# DigitalClock.net
KiCad netlist of a schematic drawn in Altium Designer
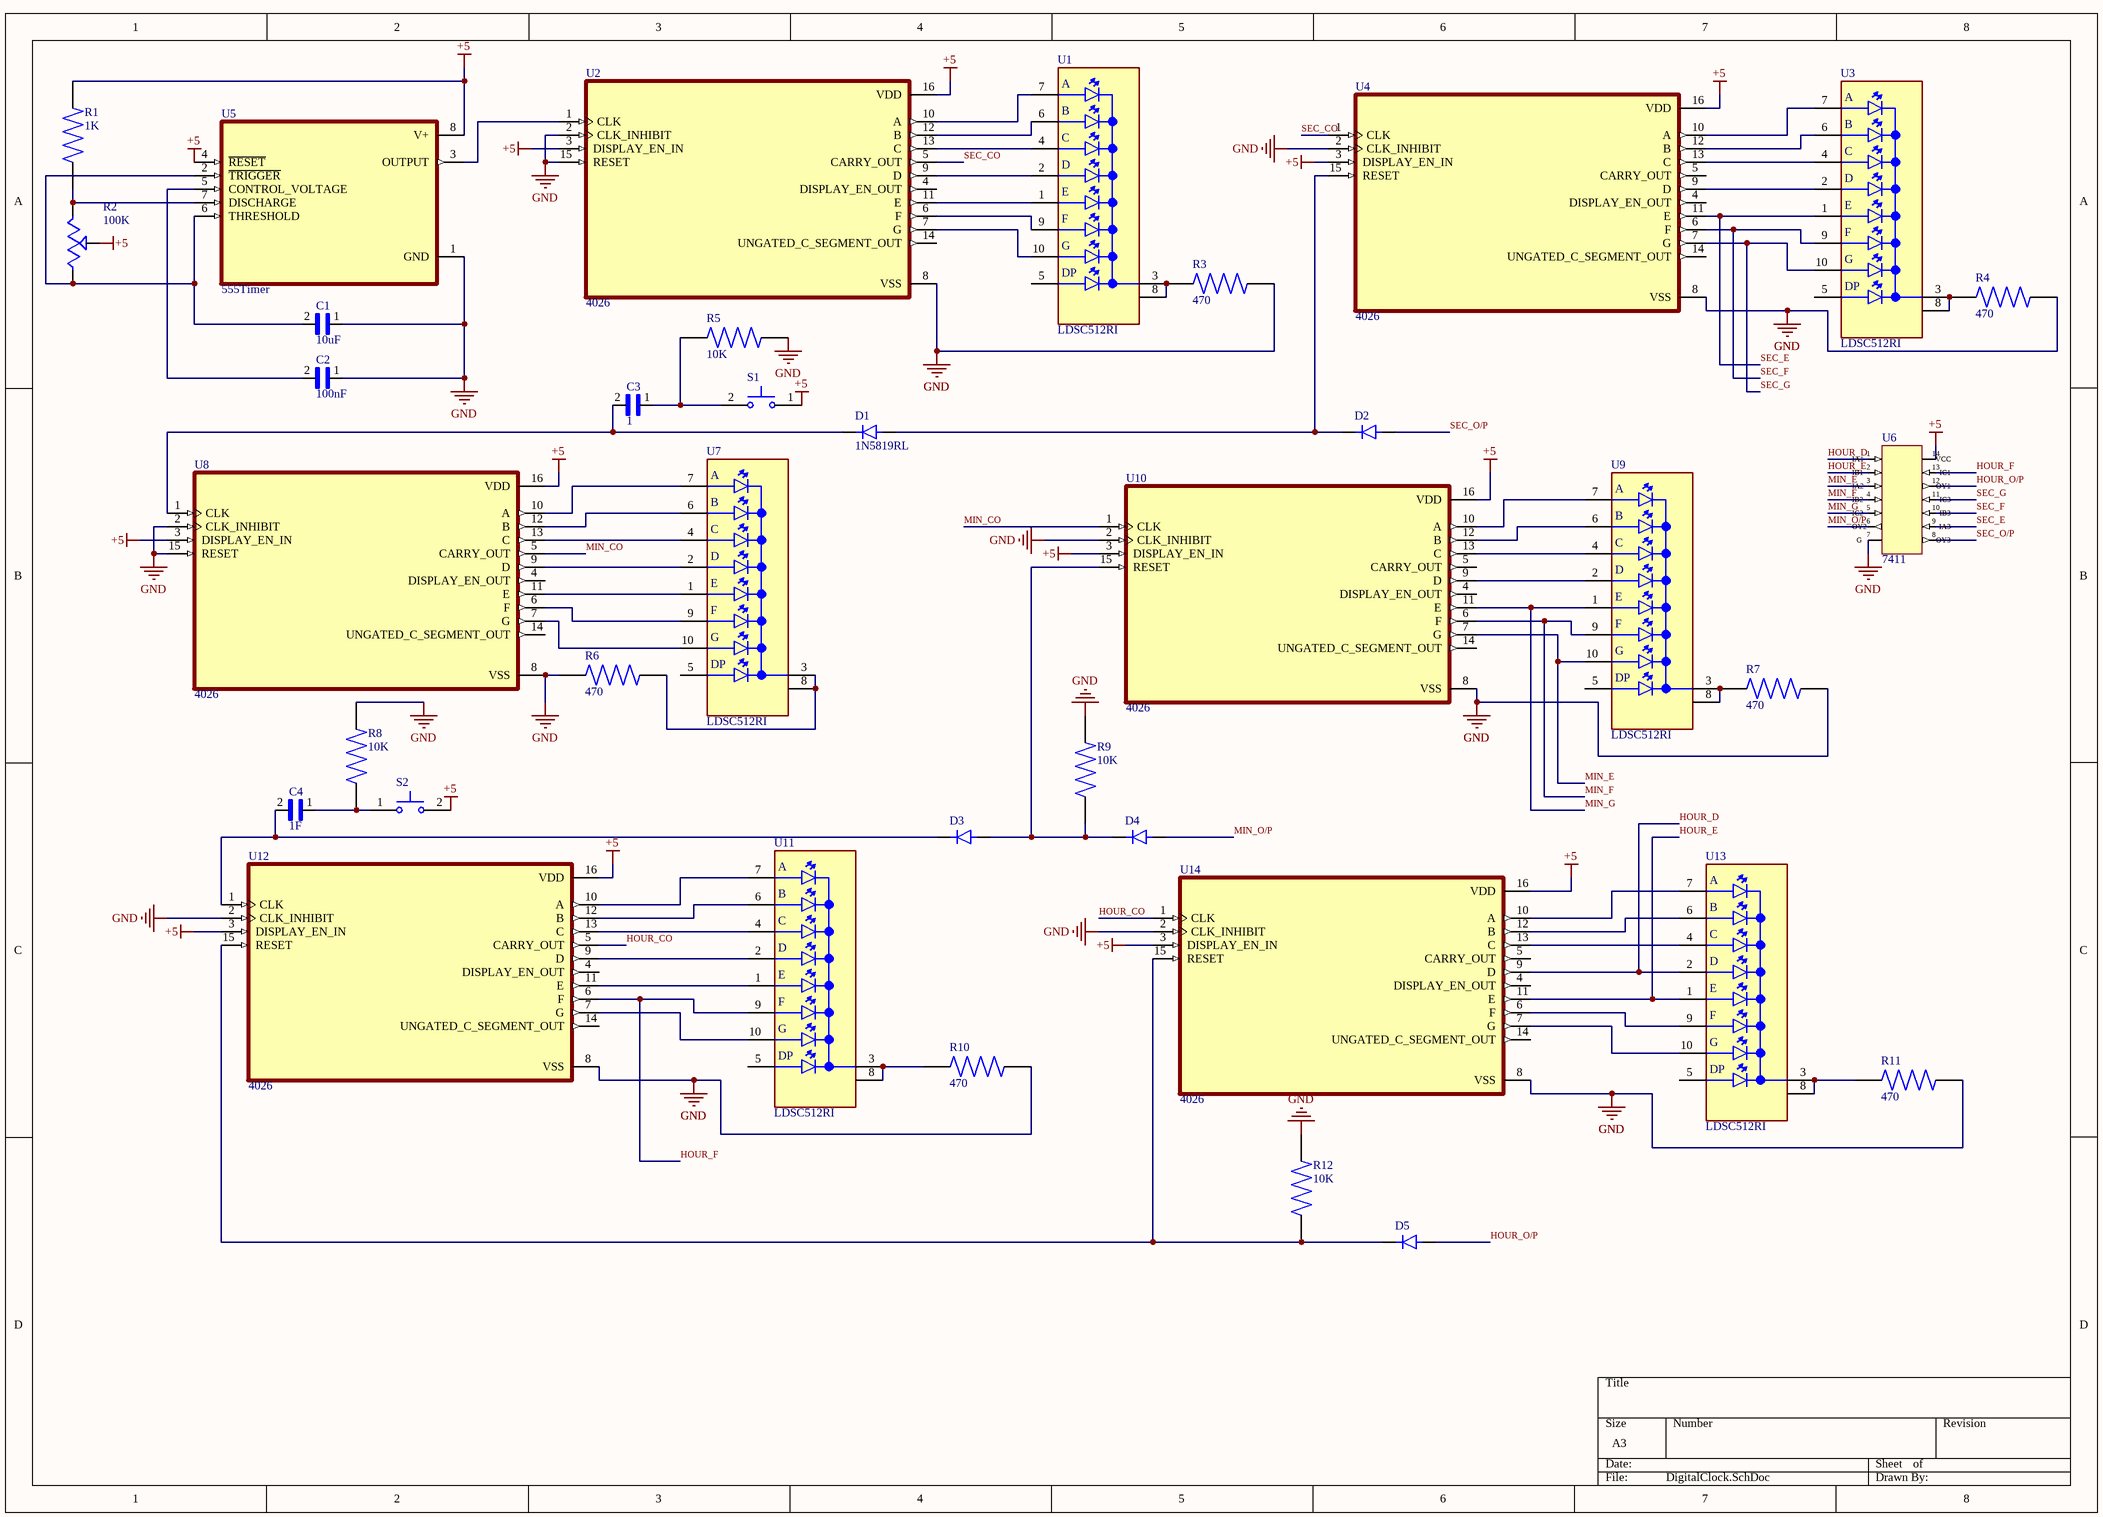
[diagram p0: DigitalClock.SchDoc]

(export (version "E")
  (design (tool "Eeschema 10.0.6"))
  (components
    (comp (ref "C1")
      (value "10uF")
      (footprint "CAPC1005X55N")
      (fields (field (name "MP") "C0402H102J5GACTU"))
      (libsource (lib "Capacitor") (part "C0402H102J5GACTU"))
    )
    (comp (ref "C2")
      (value "100nF")
      (footprint "CAPC1005X55N")
      (fields (field (name "MP") "C0402H102J5GACTU"))
      (libsource (lib "Capacitor") (part "C0402H102J5GACTU"))
    )
    (comp (ref "C3")
      (value "1")
      (footprint "CAPC1005X55N")
      (fields (field (name "MP") "C0402H102J5GACTU"))
      (libsource (lib "Capacitor") (part "C0402H102J5GACTU"))
    )
    (comp (ref "C4")
      (value "1F")
      (footprint "CAPC1005X55N")
      (fields (field (name "MP") "C0402H102J5GACTU"))
      (libsource (lib "Capacitor") (part "C0402H102J5GACTU"))
    )
    (comp (ref "D1")
      (value "1N5819RL")
      (footprint "DIOAD1036W78L470D235")
      (description "Diode Schottky 40 V 1A Through Hole Axial")
      (fields (field (name "MF") "ON Semiconductor"))
      (libsource (lib "Diode_Rectifier_Schottky") (part "1N5819RL"))
    )
    (comp (ref "D2")
      (value "1N5819RL")
      (footprint "DIOAD1036W78L470D235")
      (description "Diode Schottky 40 V 1A Through Hole Axial")
      (fields (field (name "MF") "ON Semiconductor"))
      (libsource (lib "Diode_Rectifier_Schottky") (part "1N5819RL"))
    )
    (comp (ref "D3")
      (value "1N5819RL")
      (footprint "DIOAD1036W78L470D235")
      (description "Diode Schottky 40 V 1A Through Hole Axial")
      (fields (field (name "MF") "ON Semiconductor"))
      (libsource (lib "Diode_Rectifier_Schottky") (part "1N5819RL"))
    )
    (comp (ref "D4")
      (value "1N5819RL")
      (footprint "DIOAD1036W78L470D235")
      (description "Diode Schottky 40 V 1A Through Hole Axial")
      (fields (field (name "MF") "ON Semiconductor"))
      (libsource (lib "Diode_Rectifier_Schottky") (part "1N5819RL"))
    )
    (comp (ref "D5")
      (value "1N5819RL")
      (footprint "DIOAD1036W78L470D235")
      (description "Diode Schottky 40 V 1A Through Hole Axial")
      (fields (field (name "MF") "ON Semiconductor"))
      (libsource (lib "Diode_Rectifier_Schottky") (part "1N5819RL"))
    )
    (comp (ref "R1")
      (value "1K")
      (footprint "RESAD1100W55L680D260")
      (fields (field (name "MP") "ERJU01J683C"))
      (libsource (lib "Resistance") (part "ERJU01J683C"))
    )
    (comp (ref "R2")
      (value "100K")
      (footprint "POT_RD901F-40-15R1-B100K-00DL1")
      (description "Potentiometers 9mm Linear 100K Round Shaft")
      (fields (field (name "MF") "Alpha (Taiwan)") (field (name "MP") "RD901F-40-15R1-B100K-00DL1"))
      (libsource (lib "Potentiometer_02") (part "RD901F-40-15R1-B100K-00DL1"))
    )
    (comp (ref "R3")
      (value "470")
      (footprint "TO508P1060X500X1900-2")
      (fields (field (name "MP") "ERJU01J683C"))
      (libsource (lib "Resistance") (part "ERJU01J683C"))
    )
    (comp (ref "R4")
      (value "470")
      (footprint "RES_ERJU01J683C")
      (fields (field (name "MP") "ERJU01J683C"))
      (libsource (lib "Resistance") (part "ERJU01J683C"))
    )
    (comp (ref "R5")
      (value "10K")
      (footprint "RES_ERJU01J683C")
      (fields (field (name "MP") "ERJU01J683C"))
      (libsource (lib "Resistance") (part "ERJU01J683C"))
    )
    (comp (ref "R6")
      (value "470")
      (footprint "RES_ERJU01J683C")
      (fields (field (name "MP") "ERJU01J683C"))
      (libsource (lib "Resistance") (part "ERJU01J683C"))
    )
    (comp (ref "R7")
      (value "470")
      (footprint "RES_ERJU01J683C")
      (fields (field (name "MP") "ERJU01J683C"))
      (libsource (lib "Resistance") (part "ERJU01J683C"))
    )
    (comp (ref "R8")
      (value "10K")
      (footprint "RES_ERJU01J683C")
      (fields (field (name "MP") "ERJU01J683C"))
      (libsource (lib "Resistance") (part "ERJU01J683C"))
    )
    (comp (ref "R9")
      (value "10K")
      (footprint "RES_ERJU01J683C")
      (fields (field (name "MP") "ERJU01J683C"))
      (libsource (lib "Resistance") (part "ERJU01J683C"))
    )
    (comp (ref "R10")
      (value "470")
      (footprint "RES_ERJU01J683C")
      (fields (field (name "MP") "ERJU01J683C"))
      (libsource (lib "Resistance") (part "ERJU01J683C"))
    )
    (comp (ref "R11")
      (value "470")
      (footprint "RES_ERJU01J683C")
      (fields (field (name "MP") "ERJU01J683C"))
      (libsource (lib "Resistance") (part "ERJU01J683C"))
    )
    (comp (ref "R12")
      (value "10K")
      (footprint "RES_ERJU01J683C")
      (fields (field (name "MP") "ERJU01J683C"))
      (libsource (lib "Resistance") (part "ERJU01J683C"))
    )
    (comp (ref "S1")
      (value "BUTT-2")
      (footprint "SW_BUTT-2")
      (description "Tactile Switches MINI PUSH BUTTON SWITCH 2-PIN QTY. 4")
      (fields (field (name "MF") "Gravitech"))
      (libsource (lib "PushButton02") (part "BUTT-2"))
    )
    (comp (ref "S2")
      (value "BUTT-2")
      (footprint "SW_BUTT-2")
      (description "Tactile Switches MINI PUSH BUTTON SWITCH 2-PIN QTY. 4")
      (fields (field (name "MF") "Gravitech"))
      (libsource (lib "PushButton02") (part "BUTT-2"))
    )
    (comp (ref "U1")
      (value "LDSC512RI")
      (footprint "LED_LDSC512RI")
      (fields (field (name "MF") "Lumex Optoelectronics"))
      (libsource (lib "LDSC512RI") (part "LDSC512RI"))
    )
    (comp (ref "U2")
      (value "4026")
      (footprint "DIP794W45P254L1969H508Q16")
      (fields (field (name "MF") "Texas Instruments") (field (name "MP") "CD4026BE"))
      (libsource (lib "DecadeCounter_CD4026") (part "CD4026BE"))
    )
    (comp (ref "U3")
      (value "LDSC512RI")
      (footprint "LED_LDSC512RI")
      (fields (field (name "MF") "Lumex Optoelectronics"))
      (libsource (lib "LDSC512RI") (part "LDSC512RI"))
    )
    (comp (ref "U4")
      (value "4026")
      (footprint "DIP794W45P254L1969H508Q16")
      (fields (field (name "MF") "Texas Instruments") (field (name "MP") "CD4026BE"))
      (libsource (lib "DecadeCounter_CD4026") (part "CD4026BE"))
    )
    (comp (ref "U5")
      (value "555Timer")
      (footprint "SOIC127P599X175-8N")
      (description "Worlds smallest 555 timer with low power, high accuracy and a Fmax of 3MHz 8-SOIC -40 to 85")
      (fields (field (name "MP") "LMC555CM/NOPB") (field (name "MF") "Texas Instruments"))
      (libsource (lib "555Timer") (part "LMC555CM/NOPB"))
    )
    (comp (ref "U6")
      (value "7411")
      (footprint "IC 7411")
      (description "Three Input AND Gate")
      (libsource (lib "IC7411") (part "7411"))
    )
    (comp (ref "U7")
      (value "LDSC512RI")
      (footprint "LED_LDSC512RI")
      (fields (field (name "MF") "Lumex Optoelectronics"))
      (libsource (lib "LDSC512RI") (part "LDSC512RI"))
    )
    (comp (ref "U8")
      (value "4026")
      (footprint "DIP794W45P254L1969H508Q16")
      (fields (field (name "MF") "Texas Instruments") (field (name "MP") "CD4026BE"))
      (libsource (lib "DecadeCounter_CD4026") (part "CD4026BE"))
    )
    (comp (ref "U9")
      (value "LDSC512RI")
      (footprint "LED_LDSC512RI")
      (fields (field (name "MF") "Lumex Optoelectronics"))
      (libsource (lib "LDSC512RI") (part "LDSC512RI"))
    )
    (comp (ref "U10")
      (value "4026")
      (footprint "DIP794W45P254L1969H508Q16")
      (fields (field (name "MF") "Texas Instruments") (field (name "MP") "CD4026BE"))
      (libsource (lib "DecadeCounter_CD4026") (part "CD4026BE"))
    )
    (comp (ref "U11")
      (value "LDSC512RI")
      (footprint "LED_LDSC512RI")
      (fields (field (name "MF") "Lumex Optoelectronics"))
      (libsource (lib "LDSC512RI") (part "LDSC512RI"))
    )
    (comp (ref "U12")
      (value "4026")
      (footprint "DIP794W45P254L1969H508Q16")
      (fields (field (name "MF") "Texas Instruments") (field (name "MP") "CD4026BE"))
      (libsource (lib "DecadeCounter_CD4026") (part "CD4026BE"))
    )
    (comp (ref "U13")
      (value "LDSC512RI")
      (footprint "LED_LDSC512RI")
      (fields (field (name "MF") "Lumex Optoelectronics"))
      (libsource (lib "LDSC512RI") (part "LDSC512RI"))
    )
    (comp (ref "U14")
      (value "4026")
      (footprint "DIP794W45P254L1969H508Q16")
      (fields (field (name "MF") "Texas Instruments") (field (name "MP") "CD4026BE"))
      (libsource (lib "DecadeCounter_CD4026") (part "CD4026BE"))
    )
  )
  (nets
    (net (code "1") (name "+5") (class "Default")
      (node (ref "R1") (pin "2") (pinfunction "2_2") (pintype "passive"))
      (node (ref "R2") (pin "2") (pinfunction "2_2") (pintype "passive"))
      (node (ref "S1") (pin "1") (pinfunction "1_1") (pintype "passive"))
      (node (ref "S2") (pin "2") (pinfunction "2_2") (pintype "passive"))
      (node (ref "U10") (pin "16") (pinfunction "VDD_16") (pintype "power_in"))
      (node (ref "U10") (pin "3") (pinfunction "DISPLAY_EN_IN_3") (pintype "input"))
      (node (ref "U12") (pin "16") (pinfunction "VDD_16") (pintype "power_in"))
      (node (ref "U12") (pin "3") (pinfunction "DISPLAY_EN_IN_3") (pintype "input"))
      (node (ref "U14") (pin "16") (pinfunction "VDD_16") (pintype "power_in"))
      (node (ref "U14") (pin "3") (pinfunction "DISPLAY_EN_IN_3") (pintype "input"))
      (node (ref "U2") (pin "16") (pinfunction "VDD_16") (pintype "power_in"))
      (node (ref "U2") (pin "3") (pinfunction "DISPLAY_EN_IN_3") (pintype "input"))
      (node (ref "U4") (pin "16") (pinfunction "VDD_16") (pintype "power_in"))
      (node (ref "U4") (pin "3") (pinfunction "DISPLAY_EN_IN_3") (pintype "input"))
      (node (ref "U5") (pin "4") (pinfunction "~{RESET}_4") (pintype "input"))
      (node (ref "U5") (pin "8") (pinfunction "V+_8") (pintype "power_in"))
      (node (ref "U6") (pin "14") (pinfunction "VCC_14") (pintype "power_in"))
      (node (ref "U8") (pin "16") (pinfunction "VDD_16") (pintype "power_in"))
      (node (ref "U8") (pin "3") (pinfunction "DISPLAY_EN_IN_3") (pintype "input"))
    )
    (net (code "2") (name "/HOUR_CO") (class "Default")
      (node (ref "U12") (pin "5") (pinfunction "CARRY_OUT_5") (pintype "output"))
      (node (ref "U14") (pin "1") (pinfunction "CLK_1") (pintype "input"))
    )
    (net (code "3") (name "/HOUR_D") (class "Default")
      (node (ref "U13") (pin "2") (pinfunction "D_2") (pintype "passive"))
      (node (ref "U14") (pin "9") (pinfunction "D_9") (pintype "output"))
      (node (ref "U6") (pin "1") (pinfunction "IA1_1") (pintype "input"))
    )
    (net (code "4") (name "/HOUR_E") (class "Default")
      (node (ref "U13") (pin "1") (pinfunction "E_1") (pintype "passive"))
      (node (ref "U14") (pin "11") (pinfunction "E_11") (pintype "output"))
      (node (ref "U6") (pin "2") (pinfunction "IB1_2") (pintype "input"))
    )
    (net (code "5") (name "/HOUR_F") (class "Default")
      (node (ref "U11") (pin "9") (pinfunction "F_9") (pintype "passive"))
      (node (ref "U12") (pin "6") (pinfunction "F_6") (pintype "output"))
      (node (ref "U6") (pin "13") (pinfunction "IC1_13") (pintype "input"))
    )
    (net (code "6") (name "/HOUR_O{slash}P") (class "Default")
      (node (ref "D5") (pin "A") (pinfunction "A_A") (pintype "passive"))
      (node (ref "U6") (pin "12") (pinfunction "OY1_12") (pintype "output"))
    )
    (net (code "7") (name "/MIN_CO") (class "Default")
      (node (ref "U10") (pin "1") (pinfunction "CLK_1") (pintype "input"))
      (node (ref "U8") (pin "5") (pinfunction "CARRY_OUT_5") (pintype "output"))
    )
    (net (code "8") (name "/MIN_E") (class "Default")
      (node (ref "U10") (pin "7") (pinfunction "G_7") (pintype "output"))
      (node (ref "U6") (pin "3") (pinfunction "IA2_3") (pintype "input"))
      (node (ref "U9") (pin "10") (pinfunction "G_10") (pintype "passive"))
    )
    (net (code "9") (name "/MIN_F") (class "Default")
      (node (ref "U10") (pin "6") (pinfunction "F_6") (pintype "output"))
      (node (ref "U6") (pin "4") (pinfunction "IB2_4") (pintype "input"))
      (node (ref "U9") (pin "9") (pinfunction "F_9") (pintype "passive"))
    )
    (net (code "10") (name "/MIN_G") (class "Default")
      (node (ref "U10") (pin "11") (pinfunction "E_11") (pintype "output"))
      (node (ref "U6") (pin "5") (pinfunction "IC2_5") (pintype "input"))
      (node (ref "U9") (pin "1") (pinfunction "E_1") (pintype "passive"))
    )
    (net (code "11") (name "/MIN_O{slash}P") (class "Default")
      (node (ref "D4") (pin "A") (pinfunction "A_A") (pintype "passive"))
      (node (ref "U6") (pin "6") (pinfunction "OY2_6") (pintype "output"))
    )
    (net (code "12") (name "/SEC_CO") (class "Default")
      (node (ref "U2") (pin "5") (pinfunction "CARRY_OUT_5") (pintype "output"))
      (node (ref "U4") (pin "1") (pinfunction "CLK_1") (pintype "input"))
    )
    (net (code "13") (name "/SEC_E") (class "Default")
      (node (ref "U3") (pin "1") (pinfunction "E_1") (pintype "passive"))
      (node (ref "U4") (pin "11") (pinfunction "E_11") (pintype "output"))
      (node (ref "U6") (pin "9") (pinfunction "IA3_9") (pintype "input"))
    )
    (net (code "14") (name "/SEC_F") (class "Default")
      (node (ref "U3") (pin "9") (pinfunction "F_9") (pintype "passive"))
      (node (ref "U4") (pin "6") (pinfunction "F_6") (pintype "output"))
      (node (ref "U6") (pin "10") (pinfunction "IB3_10") (pintype "input"))
    )
    (net (code "15") (name "/SEC_G") (class "Default")
      (node (ref "U3") (pin "10") (pinfunction "G_10") (pintype "passive"))
      (node (ref "U4") (pin "7") (pinfunction "G_7") (pintype "output"))
      (node (ref "U6") (pin "11") (pinfunction "IC3_11") (pintype "input"))
    )
    (net (code "16") (name "/SEC_O{slash}P") (class "Default")
      (node (ref "D2") (pin "A") (pinfunction "A_A") (pintype "passive"))
      (node (ref "U6") (pin "8") (pinfunction "OY3_8") (pintype "output"))
    )
    (net (code "17") (name "GND") (class "Default")
      (node (ref "C1") (pin "1") (pinfunction "1_1") (pintype "passive"))
      (node (ref "C2") (pin "1") (pinfunction "1_1") (pintype "passive"))
      (node (ref "R10") (pin "2") (pinfunction "2_2") (pintype "passive"))
      (node (ref "R11") (pin "2") (pinfunction "2_2") (pintype "passive"))
      (node (ref "R12") (pin "2") (pinfunction "2_2") (pintype "passive"))
      (node (ref "R3") (pin "2") (pinfunction "2_2") (pintype "passive"))
      (node (ref "R4") (pin "2") (pinfunction "2_2") (pintype "passive"))
      (node (ref "R5") (pin "1") (pinfunction "1_1") (pintype "passive"))
      (node (ref "R6") (pin "2") (pinfunction "2_2") (pintype "passive"))
      (node (ref "R7") (pin "2") (pinfunction "2_2") (pintype "passive"))
      (node (ref "R8") (pin "2") (pinfunction "2_2") (pintype "passive"))
      (node (ref "R9") (pin "2") (pinfunction "2_2") (pintype "passive"))
      (node (ref "U10") (pin "2") (pinfunction "CLK_INHIBIT_2") (pintype "input"))
      (node (ref "U10") (pin "8") (pinfunction "VSS_8") (pintype "power_in"))
      (node (ref "U12") (pin "2") (pinfunction "CLK_INHIBIT_2") (pintype "input"))
      (node (ref "U12") (pin "8") (pinfunction "VSS_8") (pintype "power_in"))
      (node (ref "U14") (pin "2") (pinfunction "CLK_INHIBIT_2") (pintype "input"))
      (node (ref "U14") (pin "8") (pinfunction "VSS_8") (pintype "power_in"))
      (node (ref "U2") (pin "15") (pinfunction "RESET_15") (pintype "input"))
      (node (ref "U2") (pin "2") (pinfunction "CLK_INHIBIT_2") (pintype "input"))
      (node (ref "U2") (pin "8") (pinfunction "VSS_8") (pintype "power_in"))
      (node (ref "U4") (pin "2") (pinfunction "CLK_INHIBIT_2") (pintype "input"))
      (node (ref "U4") (pin "8") (pinfunction "VSS_8") (pintype "power_in"))
      (node (ref "U5") (pin "1") (pinfunction "GND_1") (pintype "power_in"))
      (node (ref "U6") (pin "7") (pinfunction "G_7") (pintype "passive"))
      (node (ref "U8") (pin "15") (pinfunction "RESET_15") (pintype "input"))
      (node (ref "U8") (pin "2") (pinfunction "CLK_INHIBIT_2") (pintype "input"))
      (node (ref "U8") (pin "8") (pinfunction "VSS_8") (pintype "power_in"))
    )
    (net (code "18") (name "Net-(C3-Pad1)") (class "Default")
      (node (ref "C3") (pin "1") (pinfunction "1_1") (pintype "passive"))
      (node (ref "R5") (pin "2") (pinfunction "2_2") (pintype "passive"))
      (node (ref "S1") (pin "2") (pinfunction "2_2") (pintype "passive"))
    )
    (net (code "19") (name "Net-(C4-Pad1)") (class "Default")
      (node (ref "C4") (pin "1") (pinfunction "1_1") (pintype "passive"))
      (node (ref "R8") (pin "1") (pinfunction "1_1") (pintype "passive"))
      (node (ref "S2") (pin "1") (pinfunction "1_1") (pintype "passive"))
    )
    (net (code "20") (name "Net-(D1-K)") (class "Default")
      (node (ref "C3") (pin "2") (pinfunction "2_2") (pintype "passive"))
      (node (ref "D1") (pin "C") (pinfunction "K_C") (pintype "passive"))
      (node (ref "U8") (pin "1") (pinfunction "CLK_1") (pintype "input"))
    )
    (net (code "21") (name "Net-(D2-K)") (class "Default")
      (node (ref "D1") (pin "A") (pinfunction "A_A") (pintype "passive"))
      (node (ref "D2") (pin "C") (pinfunction "K_C") (pintype "passive"))
      (node (ref "U4") (pin "15") (pinfunction "RESET_15") (pintype "input"))
    )
    (net (code "22") (name "Net-(D3-K)") (class "Default")
      (node (ref "C4") (pin "2") (pinfunction "2_2") (pintype "passive"))
      (node (ref "D3") (pin "C") (pinfunction "K_C") (pintype "passive"))
      (node (ref "U12") (pin "1") (pinfunction "CLK_1") (pintype "input"))
    )
    (net (code "23") (name "Net-(D4-K)") (class "Default")
      (node (ref "D3") (pin "A") (pinfunction "A_A") (pintype "passive"))
      (node (ref "D4") (pin "C") (pinfunction "K_C") (pintype "passive"))
      (node (ref "R9") (pin "1") (pinfunction "1_1") (pintype "passive"))
      (node (ref "U10") (pin "15") (pinfunction "RESET_15") (pintype "input"))
    )
    (net (code "24") (name "Net-(D5-K)") (class "Default")
      (node (ref "D5") (pin "C") (pinfunction "K_C") (pintype "passive"))
      (node (ref "R12") (pin "1") (pinfunction "1_1") (pintype "passive"))
      (node (ref "U12") (pin "15") (pinfunction "RESET_15") (pintype "input"))
      (node (ref "U14") (pin "15") (pinfunction "RESET_15") (pintype "input"))
    )
    (net (code "25") (name "Net-(R3-Pad1)") (class "Default")
      (node (ref "R3") (pin "1") (pinfunction "1_1") (pintype "passive"))
      (node (ref "U1") (pin "3") (pinfunction "CC_3") (pintype "passive"))
      (node (ref "U1") (pin "8") (pinfunction "CC_8") (pintype "passive"))
    )
    (net (code "26") (name "Net-(R4-Pad1)") (class "Default")
      (node (ref "R4") (pin "1") (pinfunction "1_1") (pintype "passive"))
      (node (ref "U3") (pin "3") (pinfunction "CC_3") (pintype "passive"))
      (node (ref "U3") (pin "8") (pinfunction "CC_8") (pintype "passive"))
    )
    (net (code "27") (name "Net-(R6-Pad1)") (class "Default")
      (node (ref "R6") (pin "1") (pinfunction "1_1") (pintype "passive"))
      (node (ref "U7") (pin "3") (pinfunction "CC_3") (pintype "passive"))
      (node (ref "U7") (pin "8") (pinfunction "CC_8") (pintype "passive"))
    )
    (net (code "28") (name "Net-(R7-Pad1)") (class "Default")
      (node (ref "R7") (pin "1") (pinfunction "1_1") (pintype "passive"))
      (node (ref "U9") (pin "3") (pinfunction "CC_3") (pintype "passive"))
      (node (ref "U9") (pin "8") (pinfunction "CC_8") (pintype "passive"))
    )
    (net (code "29") (name "Net-(R10-Pad1)") (class "Default")
      (node (ref "R10") (pin "1") (pinfunction "1_1") (pintype "passive"))
      (node (ref "U11") (pin "3") (pinfunction "CC_3") (pintype "passive"))
      (node (ref "U11") (pin "8") (pinfunction "CC_8") (pintype "passive"))
    )
    (net (code "30") (name "Net-(R11-Pad1)") (class "Default")
      (node (ref "R11") (pin "1") (pinfunction "1_1") (pintype "passive"))
      (node (ref "U13") (pin "3") (pinfunction "CC_3") (pintype "passive"))
      (node (ref "U13") (pin "8") (pinfunction "CC_8") (pintype "passive"))
    )
    (net (code "31") (name "Net-(U1-A)") (class "Default")
      (node (ref "U1") (pin "7") (pinfunction "A_7") (pintype "passive"))
      (node (ref "U2") (pin "10") (pinfunction "A_10") (pintype "output"))
    )
    (net (code "32") (name "Net-(U1-B)") (class "Default")
      (node (ref "U1") (pin "6") (pinfunction "B_6") (pintype "passive"))
      (node (ref "U2") (pin "12") (pinfunction "B_12") (pintype "output"))
    )
    (net (code "33") (name "Net-(U1-C)") (class "Default")
      (node (ref "U1") (pin "4") (pinfunction "C_4") (pintype "passive"))
      (node (ref "U2") (pin "13") (pinfunction "C_13") (pintype "output"))
    )
    (net (code "34") (name "Net-(U1-D)") (class "Default")
      (node (ref "U1") (pin "2") (pinfunction "D_2") (pintype "passive"))
      (node (ref "U2") (pin "9") (pinfunction "D_9") (pintype "output"))
    )
    (net (code "35") (name "Net-(U1-E)") (class "Default")
      (node (ref "U1") (pin "1") (pinfunction "E_1") (pintype "passive"))
      (node (ref "U2") (pin "11") (pinfunction "E_11") (pintype "output"))
    )
    (net (code "36") (name "Net-(U1-F)") (class "Default")
      (node (ref "U1") (pin "9") (pinfunction "F_9") (pintype "passive"))
      (node (ref "U2") (pin "6") (pinfunction "F_6") (pintype "output"))
    )
    (net (code "37") (name "Net-(U1-G)") (class "Default")
      (node (ref "U1") (pin "10") (pinfunction "G_10") (pintype "passive"))
      (node (ref "U2") (pin "7") (pinfunction "G_7") (pintype "output"))
    )
    (net (code "38") (name "Net-(U2-CLK)") (class "Default")
      (node (ref "U2") (pin "1") (pinfunction "CLK_1") (pintype "input"))
      (node (ref "U5") (pin "3") (pinfunction "OUTPUT_3") (pintype "output"))
    )
    (net (code "39") (name "Net-(U3-A)") (class "Default")
      (node (ref "U3") (pin "7") (pinfunction "A_7") (pintype "passive"))
      (node (ref "U4") (pin "10") (pinfunction "A_10") (pintype "output"))
    )
    (net (code "40") (name "Net-(U3-B)") (class "Default")
      (node (ref "U3") (pin "6") (pinfunction "B_6") (pintype "passive"))
      (node (ref "U4") (pin "12") (pinfunction "B_12") (pintype "output"))
    )
    (net (code "41") (name "Net-(U3-C)") (class "Default")
      (node (ref "U3") (pin "4") (pinfunction "C_4") (pintype "passive"))
      (node (ref "U4") (pin "13") (pinfunction "C_13") (pintype "output"))
    )
    (net (code "42") (name "Net-(U3-D)") (class "Default")
      (node (ref "U3") (pin "2") (pinfunction "D_2") (pintype "passive"))
      (node (ref "U4") (pin "9") (pinfunction "D_9") (pintype "output"))
    )
    (net (code "43") (name "Net-(U5-CONTROL_VOLTAGE)") (class "Default")
      (node (ref "C2") (pin "2") (pinfunction "2_2") (pintype "passive"))
      (node (ref "U5") (pin "5") (pinfunction "CONTROL_VOLTAGE_5") (pintype "input"))
    )
    (net (code "44") (name "Net-(U5-DISCHARGE)") (class "Default")
      (node (ref "R1") (pin "1") (pinfunction "1_1") (pintype "passive"))
      (node (ref "R2") (pin "3") (pinfunction "3_3") (pintype "passive"))
      (node (ref "U5") (pin "7") (pinfunction "DISCHARGE_7") (pintype "input"))
    )
    (net (code "45") (name "Net-(U5-THRESHOLD)") (class "Default")
      (node (ref "C1") (pin "2") (pinfunction "2_2") (pintype "passive"))
      (node (ref "R2") (pin "1") (pinfunction "1_1") (pintype "passive"))
      (node (ref "U5") (pin "2") (pinfunction "~{TRIGGER}_2") (pintype "input"))
      (node (ref "U5") (pin "6") (pinfunction "THRESHOLD_6") (pintype "input"))
    )
    (net (code "46") (name "Net-(U7-A)") (class "Default")
      (node (ref "U7") (pin "7") (pinfunction "A_7") (pintype "passive"))
      (node (ref "U8") (pin "10") (pinfunction "A_10") (pintype "output"))
    )
    (net (code "47") (name "Net-(U7-B)") (class "Default")
      (node (ref "U7") (pin "6") (pinfunction "B_6") (pintype "passive"))
      (node (ref "U8") (pin "12") (pinfunction "B_12") (pintype "output"))
    )
    (net (code "48") (name "Net-(U7-C)") (class "Default")
      (node (ref "U7") (pin "4") (pinfunction "C_4") (pintype "passive"))
      (node (ref "U8") (pin "13") (pinfunction "C_13") (pintype "output"))
    )
    (net (code "49") (name "Net-(U7-D)") (class "Default")
      (node (ref "U7") (pin "2") (pinfunction "D_2") (pintype "passive"))
      (node (ref "U8") (pin "9") (pinfunction "D_9") (pintype "output"))
    )
    (net (code "50") (name "Net-(U7-E)") (class "Default")
      (node (ref "U7") (pin "1") (pinfunction "E_1") (pintype "passive"))
      (node (ref "U8") (pin "11") (pinfunction "E_11") (pintype "output"))
    )
    (net (code "51") (name "Net-(U7-F)") (class "Default")
      (node (ref "U7") (pin "9") (pinfunction "F_9") (pintype "passive"))
      (node (ref "U8") (pin "6") (pinfunction "F_6") (pintype "output"))
    )
    (net (code "52") (name "Net-(U7-G)") (class "Default")
      (node (ref "U7") (pin "10") (pinfunction "G_10") (pintype "passive"))
      (node (ref "U8") (pin "7") (pinfunction "G_7") (pintype "output"))
    )
    (net (code "53") (name "Net-(U10-A)") (class "Default")
      (node (ref "U10") (pin "10") (pinfunction "A_10") (pintype "output"))
      (node (ref "U9") (pin "7") (pinfunction "A_7") (pintype "passive"))
    )
    (net (code "54") (name "Net-(U10-B)") (class "Default")
      (node (ref "U10") (pin "12") (pinfunction "B_12") (pintype "output"))
      (node (ref "U9") (pin "6") (pinfunction "B_6") (pintype "passive"))
    )
    (net (code "55") (name "Net-(U10-C)") (class "Default")
      (node (ref "U10") (pin "13") (pinfunction "C_13") (pintype "output"))
      (node (ref "U9") (pin "4") (pinfunction "C_4") (pintype "passive"))
    )
    (net (code "56") (name "Net-(U10-D)") (class "Default")
      (node (ref "U10") (pin "9") (pinfunction "D_9") (pintype "output"))
      (node (ref "U9") (pin "2") (pinfunction "D_2") (pintype "passive"))
    )
    (net (code "57") (name "Net-(U11-A)") (class "Default")
      (node (ref "U11") (pin "7") (pinfunction "A_7") (pintype "passive"))
      (node (ref "U12") (pin "10") (pinfunction "A_10") (pintype "output"))
    )
    (net (code "58") (name "Net-(U11-B)") (class "Default")
      (node (ref "U11") (pin "6") (pinfunction "B_6") (pintype "passive"))
      (node (ref "U12") (pin "12") (pinfunction "B_12") (pintype "output"))
    )
    (net (code "59") (name "Net-(U11-C)") (class "Default")
      (node (ref "U11") (pin "4") (pinfunction "C_4") (pintype "passive"))
      (node (ref "U12") (pin "13") (pinfunction "C_13") (pintype "output"))
    )
    (net (code "60") (name "Net-(U11-D)") (class "Default")
      (node (ref "U11") (pin "2") (pinfunction "D_2") (pintype "passive"))
      (node (ref "U12") (pin "9") (pinfunction "D_9") (pintype "output"))
    )
    (net (code "61") (name "Net-(U11-E)") (class "Default")
      (node (ref "U11") (pin "1") (pinfunction "E_1") (pintype "passive"))
      (node (ref "U12") (pin "11") (pinfunction "E_11") (pintype "output"))
    )
    (net (code "62") (name "Net-(U11-G)") (class "Default")
      (node (ref "U11") (pin "10") (pinfunction "G_10") (pintype "passive"))
      (node (ref "U12") (pin "7") (pinfunction "G_7") (pintype "output"))
    )
    (net (code "63") (name "Net-(U13-A)") (class "Default")
      (node (ref "U13") (pin "7") (pinfunction "A_7") (pintype "passive"))
      (node (ref "U14") (pin "10") (pinfunction "A_10") (pintype "output"))
    )
    (net (code "64") (name "Net-(U13-B)") (class "Default")
      (node (ref "U13") (pin "6") (pinfunction "B_6") (pintype "passive"))
      (node (ref "U14") (pin "12") (pinfunction "B_12") (pintype "output"))
    )
    (net (code "65") (name "Net-(U13-C)") (class "Default")
      (node (ref "U13") (pin "4") (pinfunction "C_4") (pintype "passive"))
      (node (ref "U14") (pin "13") (pinfunction "C_13") (pintype "output"))
    )
    (net (code "66") (name "Net-(U13-F)") (class "Default")
      (node (ref "U13") (pin "9") (pinfunction "F_9") (pintype "passive"))
      (node (ref "U14") (pin "6") (pinfunction "F_6") (pintype "output"))
    )
    (net (code "67") (name "Net-(U13-G)") (class "Default")
      (node (ref "U13") (pin "10") (pinfunction "G_10") (pintype "passive"))
      (node (ref "U14") (pin "7") (pinfunction "G_7") (pintype "output"))
    )
    (net (code "68") (name "unconnected-(U1-DP-Pad5)") (class "Default")
      (node (ref "U1") (pin "5") (pinfunction "DP_5") (pintype "passive"))
    )
    (net (code "69") (name "unconnected-(U2-DISPLAY_EN_OUT-Pad4)") (class "Default")
      (node (ref "U2") (pin "4") (pinfunction "DISPLAY_EN_OUT_4") (pintype "output"))
    )
    (net (code "70") (name "unconnected-(U2-UNGATED_C_SEGMENT_OUT-Pad14)") (class "Default")
      (node (ref "U2") (pin "14") (pinfunction "UNGATED_C_SEGMENT_OUT_14") (pintype "output"))
    )
    (net (code "71") (name "unconnected-(U3-DP-Pad5)") (class "Default")
      (node (ref "U3") (pin "5") (pinfunction "DP_5") (pintype "passive"))
    )
    (net (code "72") (name "unconnected-(U4-CARRY_OUT-Pad5)") (class "Default")
      (node (ref "U4") (pin "5") (pinfunction "CARRY_OUT_5") (pintype "output"))
    )
    (net (code "73") (name "unconnected-(U4-DISPLAY_EN_OUT-Pad4)") (class "Default")
      (node (ref "U4") (pin "4") (pinfunction "DISPLAY_EN_OUT_4") (pintype "output"))
    )
    (net (code "74") (name "unconnected-(U4-UNGATED_C_SEGMENT_OUT-Pad14)") (class "Default")
      (node (ref "U4") (pin "14") (pinfunction "UNGATED_C_SEGMENT_OUT_14") (pintype "output"))
    )
    (net (code "75") (name "unconnected-(U7-DP-Pad5)") (class "Default")
      (node (ref "U7") (pin "5") (pinfunction "DP_5") (pintype "passive"))
    )
    (net (code "76") (name "unconnected-(U8-DISPLAY_EN_OUT-Pad4)") (class "Default")
      (node (ref "U8") (pin "4") (pinfunction "DISPLAY_EN_OUT_4") (pintype "output"))
    )
    (net (code "77") (name "unconnected-(U8-UNGATED_C_SEGMENT_OUT-Pad14)") (class "Default")
      (node (ref "U8") (pin "14") (pinfunction "UNGATED_C_SEGMENT_OUT_14") (pintype "output"))
    )
    (net (code "78") (name "unconnected-(U9-DP-Pad5)") (class "Default")
      (node (ref "U9") (pin "5") (pinfunction "DP_5") (pintype "passive"))
    )
    (net (code "79") (name "unconnected-(U10-CARRY_OUT-Pad5)") (class "Default")
      (node (ref "U10") (pin "5") (pinfunction "CARRY_OUT_5") (pintype "output"))
    )
    (net (code "80") (name "unconnected-(U10-DISPLAY_EN_OUT-Pad4)") (class "Default")
      (node (ref "U10") (pin "4") (pinfunction "DISPLAY_EN_OUT_4") (pintype "output"))
    )
    (net (code "81") (name "unconnected-(U10-UNGATED_C_SEGMENT_OUT-Pad14)") (class "Default")
      (node (ref "U10") (pin "14") (pinfunction "UNGATED_C_SEGMENT_OUT_14") (pintype "output"))
    )
    (net (code "82") (name "unconnected-(U11-DP-Pad5)") (class "Default")
      (node (ref "U11") (pin "5") (pinfunction "DP_5") (pintype "passive"))
    )
    (net (code "83") (name "unconnected-(U12-DISPLAY_EN_OUT-Pad4)") (class "Default")
      (node (ref "U12") (pin "4") (pinfunction "DISPLAY_EN_OUT_4") (pintype "output"))
    )
    (net (code "84") (name "unconnected-(U12-UNGATED_C_SEGMENT_OUT-Pad14)") (class "Default")
      (node (ref "U12") (pin "14") (pinfunction "UNGATED_C_SEGMENT_OUT_14") (pintype "output"))
    )
    (net (code "85") (name "unconnected-(U13-DP-Pad5)") (class "Default")
      (node (ref "U13") (pin "5") (pinfunction "DP_5") (pintype "passive"))
    )
    (net (code "86") (name "unconnected-(U14-CARRY_OUT-Pad5)") (class "Default")
      (node (ref "U14") (pin "5") (pinfunction "CARRY_OUT_5") (pintype "output"))
    )
    (net (code "87") (name "unconnected-(U14-DISPLAY_EN_OUT-Pad4)") (class "Default")
      (node (ref "U14") (pin "4") (pinfunction "DISPLAY_EN_OUT_4") (pintype "output"))
    )
    (net (code "88") (name "unconnected-(U14-UNGATED_C_SEGMENT_OUT-Pad14)") (class "Default")
      (node (ref "U14") (pin "14") (pinfunction "UNGATED_C_SEGMENT_OUT_14") (pintype "output"))
    )
  )
)
